# KeyB_1.net
KiCad netlist of a schematic drawn in EAGLE
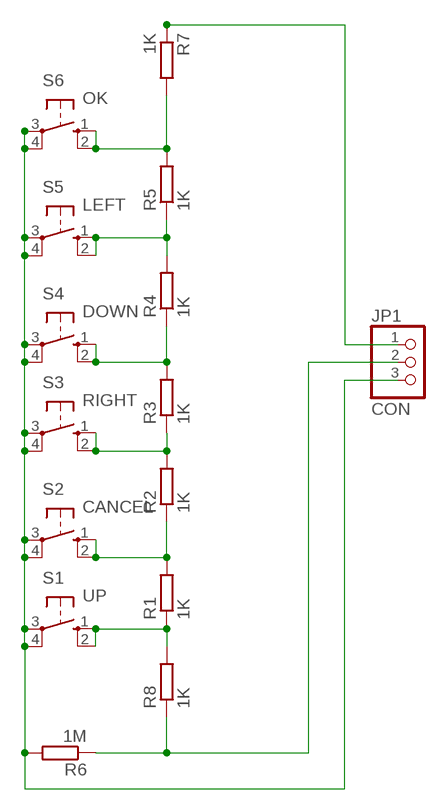
[diagram p0: schematic, sheet 1]

(export (version "E")
  (design (tool "Eeschema 10.0.6"))
  (components
    (comp (ref "JP1")
      (value "CON")
      (footprint "eagle-import:1X03")
      (libsource (lib "eagle-import") (part "PINHD-1X3"))
    )
    (comp (ref "R1")
      (value "1K")
      (footprint "eagle-import:R1206W")
      (libsource (lib "eagle-import") (part "R-EU_R1206W"))
    )
    (comp (ref "R2")
      (value "1K")
      (footprint "eagle-import:R1206W")
      (libsource (lib "eagle-import") (part "R-EU_R1206W"))
    )
    (comp (ref "R3")
      (value "1K")
      (footprint "eagle-import:R1206W")
      (libsource (lib "eagle-import") (part "R-EU_R1206W"))
    )
    (comp (ref "R4")
      (value "1K")
      (footprint "eagle-import:R1206W")
      (libsource (lib "eagle-import") (part "R-EU_R1206W"))
    )
    (comp (ref "R5")
      (value "1K")
      (footprint "eagle-import:R1206W")
      (libsource (lib "eagle-import") (part "R-EU_R1206W"))
    )
    (comp (ref "R6")
      (value "1M")
      (footprint "eagle-import:R1206W")
      (libsource (lib "eagle-import") (part "R-EU_R1206W"))
    )
    (comp (ref "R7")
      (value "1K")
      (footprint "eagle-import:R1206W")
      (libsource (lib "eagle-import") (part "R-EU_R1206W"))
    )
    (comp (ref "R8")
      (value "1K")
      (footprint "eagle-import:R1206W")
      (libsource (lib "eagle-import") (part "R-EU_R1206W"))
    )
    (comp (ref "S1")
      (value "UP")
      (footprint "eagle-import:B3F-10XX")
      (fields (field (name "MPN") "B3F-1000"))
      (libsource (lib "eagle-import") (part "10-XX"))
    )
    (comp (ref "S2")
      (value "CANCEL")
      (footprint "eagle-import:B3F-10XX")
      (fields (field (name "MPN") "B3F-1000"))
      (libsource (lib "eagle-import") (part "10-XX"))
    )
    (comp (ref "S3")
      (value "RIGHT")
      (footprint "eagle-import:B3F-10XX")
      (fields (field (name "MPN") "B3F-1000"))
      (libsource (lib "eagle-import") (part "10-XX"))
    )
    (comp (ref "S4")
      (value "DOWN")
      (footprint "eagle-import:B3F-10XX")
      (fields (field (name "MPN") "B3F-1000"))
      (libsource (lib "eagle-import") (part "10-XX"))
    )
    (comp (ref "S5")
      (value "LEFT")
      (footprint "eagle-import:B3F-10XX")
      (fields (field (name "MPN") "B3F-1000"))
      (libsource (lib "eagle-import") (part "10-XX"))
    )
    (comp (ref "S6")
      (value "OK")
      (footprint "eagle-import:B3F-10XX")
      (fields (field (name "MPN") "B3F-1000"))
      (libsource (lib "eagle-import") (part "10-XX"))
    )
  )
  (nets
    (net (code "1") (name "Net-(JP1-Pad1)") (class "Default")
      (node (ref "JP1") (pin "1") (pinfunction "1_1") (pintype "passive"))
      (node (ref "R7") (pin "1") (pinfunction "1_1") (pintype "passive"))
    )
    (net (code "2") (name "Net-(JP1-Pad2)") (class "Default")
      (node (ref "JP1") (pin "2") (pinfunction "2_2") (pintype "passive"))
      (node (ref "R6") (pin "1") (pinfunction "1_1") (pintype "passive"))
      (node (ref "R8") (pin "1") (pinfunction "1_1") (pintype "passive"))
    )
    (net (code "3") (name "Net-(S1-P)") (class "Default")
      (node (ref "JP1") (pin "3") (pinfunction "3_3") (pintype "passive"))
      (node (ref "R6") (pin "2") (pinfunction "2_2") (pintype "passive"))
      (node (ref "S1") (pin "3") (pinfunction "P_3") (pintype "passive"))
      (node (ref "S1") (pin "4") (pinfunction "P1_4") (pintype "passive"))
      (node (ref "S2") (pin "3") (pinfunction "P_3") (pintype "passive"))
      (node (ref "S2") (pin "4") (pinfunction "P1_4") (pintype "passive"))
      (node (ref "S3") (pin "3") (pinfunction "P_3") (pintype "passive"))
      (node (ref "S3") (pin "4") (pinfunction "P1_4") (pintype "passive"))
      (node (ref "S4") (pin "3") (pinfunction "P_3") (pintype "passive"))
      (node (ref "S4") (pin "4") (pinfunction "P1_4") (pintype "passive"))
      (node (ref "S5") (pin "3") (pinfunction "P_3") (pintype "passive"))
      (node (ref "S5") (pin "4") (pinfunction "P1_4") (pintype "passive"))
      (node (ref "S6") (pin "3") (pinfunction "P_3") (pintype "passive"))
      (node (ref "S6") (pin "4") (pinfunction "P1_4") (pintype "passive"))
    )
    (net (code "4") (name "Net-(S1-S)") (class "Default")
      (node (ref "R1") (pin "1") (pinfunction "1_1") (pintype "passive"))
      (node (ref "R8") (pin "2") (pinfunction "2_2") (pintype "passive"))
      (node (ref "S1") (pin "1") (pinfunction "S_1") (pintype "passive"))
      (node (ref "S1") (pin "2") (pinfunction "S1_2") (pintype "passive"))
    )
    (net (code "5") (name "Net-(S2-S)") (class "Default")
      (node (ref "R1") (pin "2") (pinfunction "2_2") (pintype "passive"))
      (node (ref "R2") (pin "1") (pinfunction "1_1") (pintype "passive"))
      (node (ref "S2") (pin "1") (pinfunction "S_1") (pintype "passive"))
      (node (ref "S2") (pin "2") (pinfunction "S1_2") (pintype "passive"))
    )
    (net (code "6") (name "Net-(S3-S)") (class "Default")
      (node (ref "R2") (pin "2") (pinfunction "2_2") (pintype "passive"))
      (node (ref "R3") (pin "1") (pinfunction "1_1") (pintype "passive"))
      (node (ref "S3") (pin "1") (pinfunction "S_1") (pintype "passive"))
      (node (ref "S3") (pin "2") (pinfunction "S1_2") (pintype "passive"))
    )
    (net (code "7") (name "Net-(S4-S)") (class "Default")
      (node (ref "R3") (pin "2") (pinfunction "2_2") (pintype "passive"))
      (node (ref "R4") (pin "1") (pinfunction "1_1") (pintype "passive"))
      (node (ref "S4") (pin "1") (pinfunction "S_1") (pintype "passive"))
      (node (ref "S4") (pin "2") (pinfunction "S1_2") (pintype "passive"))
    )
    (net (code "8") (name "Net-(S5-S)") (class "Default")
      (node (ref "R4") (pin "2") (pinfunction "2_2") (pintype "passive"))
      (node (ref "R5") (pin "1") (pinfunction "1_1") (pintype "passive"))
      (node (ref "S5") (pin "1") (pinfunction "S_1") (pintype "passive"))
      (node (ref "S5") (pin "2") (pinfunction "S1_2") (pintype "passive"))
    )
    (net (code "9") (name "Net-(S6-S)") (class "Default")
      (node (ref "R5") (pin "2") (pinfunction "2_2") (pintype "passive"))
      (node (ref "R7") (pin "2") (pinfunction "2_2") (pintype "passive"))
      (node (ref "S6") (pin "1") (pinfunction "S_1") (pintype "passive"))
      (node (ref "S6") (pin "2") (pinfunction "S1_2") (pintype "passive"))
    )
  )
)
